# power_sys_sch.net
KiCad netlist of a schematic drawn in Altium Designer
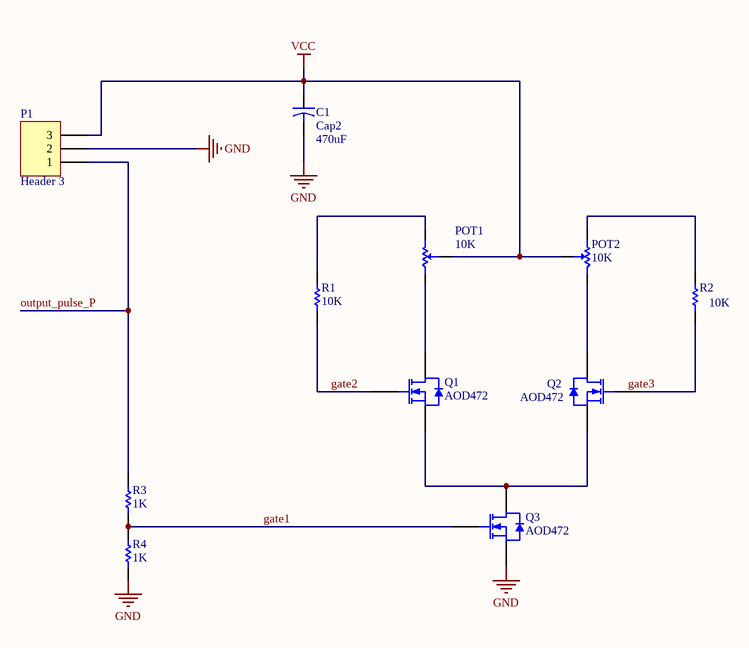
[diagram p0: power_sys_sch.SchDoc]

(export (version "E")
  (design (tool "Eeschema 10.0.6"))
  (components
    (comp (ref "C1")
      (value "Cap2")
      (footprint "CAPR5-4X5")
      (description "Capacitor")
      (fields (field (name "ALTIUM_VALUE") "470uF") (field (name "PUBLISHER") "Altium Limited"))
      (libsource (lib "Miscellaneous Devices") (part "Cap2"))
    )
    (comp (ref "P1")
      (value "Header 3")
      (footprint "HDR1X3")
      (description "Header, 3-Pin")
      (fields (field (name "PUBLISHER") "Altium Limited"))
      (libsource (lib "Miscellaneous Connectors") (part "Header 3"))
    )
    (comp (ref "POT1")
      (value "10K")
      (footprint "POT")
      (description "Variable Resistor")
      (libsource (lib "Altium") (part "POT"))
    )
    (comp (ref "POT2")
      (value "10K")
      (footprint "POT")
      (description "Variable Resistor")
      (libsource (lib "Altium") (part "POT"))
    )
    (comp (ref "Q1")
      (value "AOD472")
      (footprint "TO252-3L")
      (description "N-channel MOSFET")
      (fields (field (name "PUBLISHER") "Abbas Basereh"))
      (libsource (lib "Altium") (part "AOD472"))
    )
    (comp (ref "Q2")
      (value "AOD472")
      (footprint "TO252-3L")
      (description "N-channel MOSFET")
      (fields (field (name "PUBLISHER") "Abbas Basereh"))
      (libsource (lib "Altium") (part "AOD472"))
    )
    (comp (ref "Q3")
      (value "AOD472")
      (footprint "TO252-3L")
      (description "N-channel MOSFET")
      (fields (field (name "PUBLISHER") "Abbas Basereh"))
      (libsource (lib "Altium") (part "AOD472"))
    )
    (comp (ref "R1")
      (value "10K")
      (footprint "RESC4817X04N")
      (description "RES 1206")
      (fields (field (name "DESIGNER") "Abbas Basereh"))
      (libsource (lib "Altium") (part "RES 1206 0.25W"))
    )
    (comp (ref "R2")
      (value "10K")
      (footprint "RESC4817X04N")
      (description "RES 1206")
      (fields (field (name "DESIGNER") "Abbas Basereh"))
      (libsource (lib "Altium") (part "RES 1206 0.25W"))
    )
    (comp (ref "R3")
      (value "1K")
      (footprint "RESC4817X04N")
      (description "RES 1206")
      (fields (field (name "DESIGNER") "Abbas Basereh"))
      (libsource (lib "Altium") (part "RES 1206 0.25W"))
    )
    (comp (ref "R4")
      (value "1K")
      (footprint "RESC4817X04N")
      (description "RES 1206")
      (fields (field (name "DESIGNER") "Abbas Basereh"))
      (libsource (lib "Altium") (part "RES 1206 0.25W"))
    )
  )
  (nets
    (net (code "1") (name "/gate1") (class "Default")
      (node (ref "Q3") (pin "1") (pinfunction "G_1") (pintype "passive"))
      (node (ref "R3") (pin "1") (pinfunction "1_1") (pintype "passive"))
      (node (ref "R4") (pin "2") (pinfunction "2_2") (pintype "passive"))
    )
    (net (code "2") (name "/gate2") (class "Default")
      (node (ref "Q1") (pin "1") (pinfunction "G_1") (pintype "passive"))
      (node (ref "R1") (pin "1") (pinfunction "1_1") (pintype "passive"))
    )
    (net (code "4") (name "/output_pulse_P") (class "Default")
      (node (ref "P1") (pin "1") (pinfunction "1_1") (pintype "passive"))
      (node (ref "R3") (pin "2") (pinfunction "2_2") (pintype "passive"))
    )
    (net (code "5") (name "GND") (class "Default")
      (node (ref "C1") (pin "2") (pinfunction "2_2") (pintype "passive"))
      (node (ref "P1") (pin "2") (pinfunction "2_2") (pintype "passive"))
      (node (ref "Q3") (pin "3") (pinfunction "S_3") (pintype "passive"))
      (node (ref "R4") (pin "1") (pinfunction "1_1") (pintype "passive"))
    )
    (net (code "6") (name "Net-(POT1-CCW)") (class "Default")
      (node (ref "POT1") (pin "1") (pinfunction "CCW_1") (pintype "passive"))
      (node (ref "Q1") (pin "4") (pinfunction "D_4") (pintype "passive"))
    )
    (net (code "7") (name "Net-(POT1-CW)") (class "Default")
      (node (ref "POT1") (pin "2") (pinfunction "CW_2") (pintype "passive"))
      (node (ref "R1") (pin "2") (pinfunction "2_2") (pintype "passive"))
    )
    (net (code "8") (name "Net-(POT2-CCW)") (class "Default")
      (node (ref "POT2") (pin "1") (pinfunction "CCW_1") (pintype "passive"))
      (node (ref "Q2") (pin "4") (pinfunction "D_4") (pintype "passive"))
    )
    (net (code "9") (name "Net-(POT2-CW)") (class "Default")
      (node (ref "POT2") (pin "2") (pinfunction "CW_2") (pintype "passive"))
      (node (ref "R2") (pin "2") (pinfunction "2_2") (pintype "passive"))
    )
    (net (code "10") (name "Net-(Q1-S)") (class "Default")
      (node (ref "Q1") (pin "3") (pinfunction "S_3") (pintype "passive"))
      (node (ref "Q2") (pin "3") (pinfunction "S_3") (pintype "passive"))
      (node (ref "Q3") (pin "4") (pinfunction "D_4") (pintype "passive"))
    )
    (net (code "11") (name "Net-(Q2-G)") (class "Default")
      (node (ref "Q2") (pin "1") (pinfunction "G_1") (pintype "passive"))
      (node (ref "R2") (pin "1") (pinfunction "1_1") (pintype "passive"))
    )
    (net (code "12") (name "VCC") (class "Default")
      (node (ref "C1") (pin "1") (pinfunction "1_1") (pintype "passive"))
      (node (ref "P1") (pin "3") (pinfunction "3_3") (pintype "passive"))
      (node (ref "POT1") (pin "3") (pinfunction "SetPoint_3") (pintype "passive"))
      (node (ref "POT2") (pin "3") (pinfunction "SetPoint_3") (pintype "passive"))
    )
  )
)
